# janus.net
KiCad netlist of a schematic drawn in EAGLE
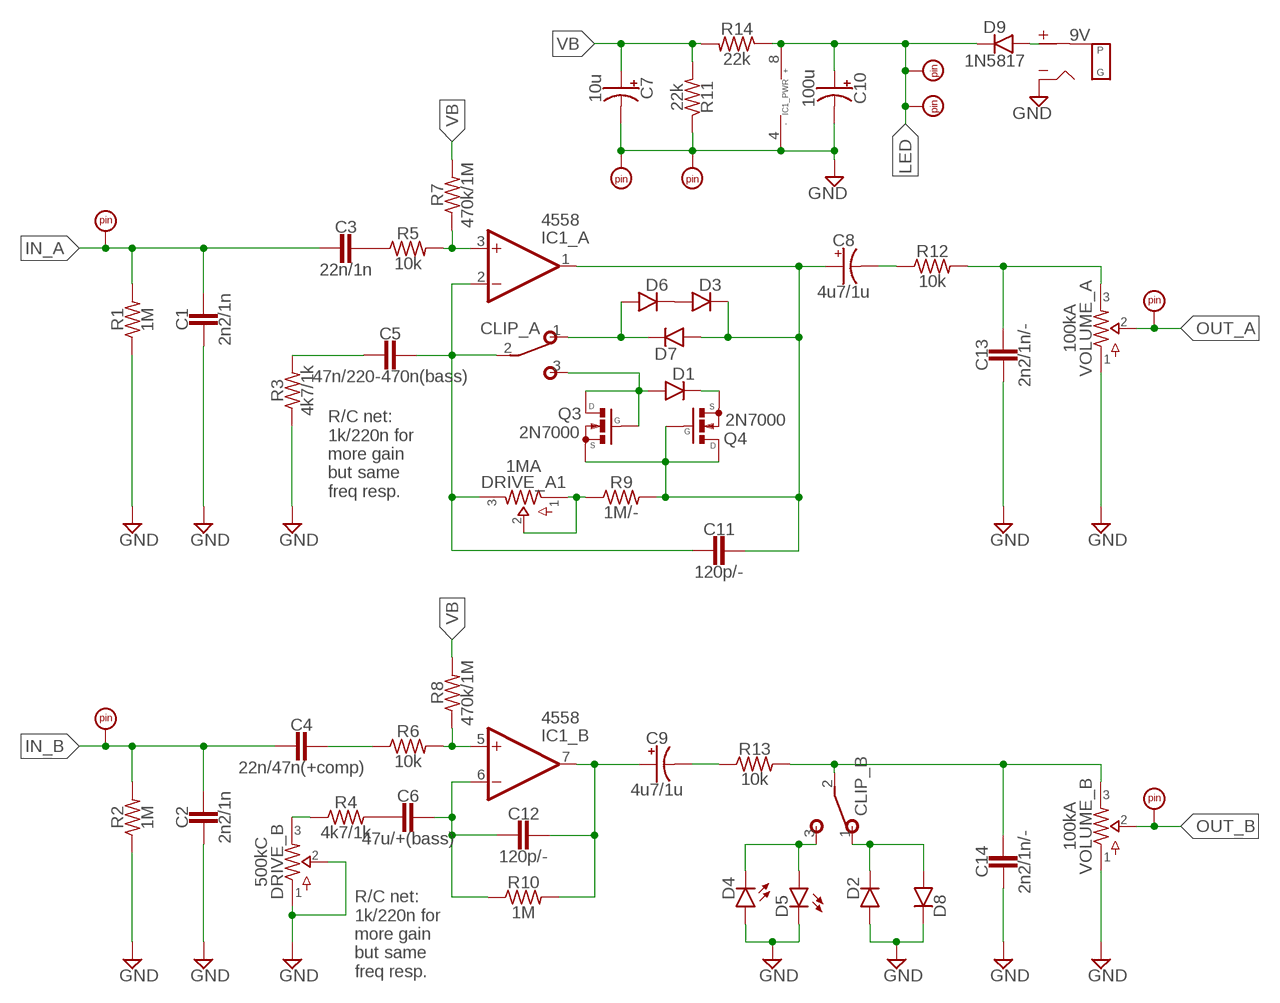
[diagram p0: schematic, sheet 1]

(export (version "E")
  (design (tool "Eeschema 10.0.6"))
  (components
    (comp (ref "9V")
      (value "DC_MONO")
      (footprint "eagle-import:DC")
      (libsource (lib "eagle-import") (part "DC_MONO"))
    )
    (comp (ref "C1")
      (value "2n2/1n")
      (footprint "eagle-import:050X030_025_2")
      (libsource (lib "eagle-import") (part "CER/FILM2"))
    )
    (comp (ref "C2")
      (value "2n2/1n")
      (footprint "eagle-import:050X030_025_2")
      (libsource (lib "eagle-import") (part "CER/FILM2"))
    )
    (comp (ref "C3")
      (value "22n/1n")
      (footprint "eagle-import:050X030_025_2")
      (libsource (lib "eagle-import") (part "CER/FILM2"))
    )
    (comp (ref "C4")
      (value "22n/47n(+comp)")
      (footprint "eagle-import:050X030_025_2")
      (libsource (lib "eagle-import") (part "CER/FILM2"))
    )
    (comp (ref "C5")
      (value "47n/220-470n(bass)")
      (footprint "eagle-import:050X030_025_2")
      (libsource (lib "eagle-import") (part "CER/FILM2"))
    )
    (comp (ref "C6")
      (value "47u/+(bass)")
      (footprint "eagle-import:050X030_025_2")
      (libsource (lib "eagle-import") (part "CER/FILM2"))
    )
    (comp (ref "C7")
      (value "10u")
      (footprint "eagle-import:050_020_1")
      (libsource (lib "eagle-import") (part "0501"))
    )
    (comp (ref "C8")
      (value "4u7/1u")
      (footprint "eagle-import:050_020_1")
      (libsource (lib "eagle-import") (part "0501"))
    )
    (comp (ref "C9")
      (value "4u7/1u")
      (footprint "eagle-import:050_020_1")
      (libsource (lib "eagle-import") (part "0501"))
    )
    (comp (ref "C10")
      (value "100u")
      (footprint "eagle-import:050_020_1")
      (libsource (lib "eagle-import") (part "0501"))
    )
    (comp (ref "C11")
      (value "120p/-")
      (footprint "eagle-import:050X030_025_2")
      (libsource (lib "eagle-import") (part "CER/FILM2"))
    )
    (comp (ref "C12")
      (value "120p/-")
      (footprint "eagle-import:050X030_025_2")
      (libsource (lib "eagle-import") (part "CER/FILM2"))
    )
    (comp (ref "C13")
      (value "2n2/1n/-")
      (footprint "eagle-import:050X030_025_2")
      (libsource (lib "eagle-import") (part "CER/FILM2"))
    )
    (comp (ref "C14")
      (value "2n2/1n/-")
      (footprint "eagle-import:050X030_025_2")
      (libsource (lib "eagle-import") (part "CER/FILM2"))
    )
    (comp (ref "CLIP_A")
      (value "SPDTPADS")
      (footprint "eagle-import:SPDT")
      (libsource (lib "eagle-import") (part "SPDTPADS"))
    )
    (comp (ref "CLIP_B")
      (value "SPDTPADS")
      (footprint "eagle-import:SPDT")
      (libsource (lib "eagle-import") (part "SPDTPADS"))
    )
    (comp (ref "D1")
      (value "DO35.2")
      (footprint "eagle-import:DO35-2")
      (libsource (lib "eagle-import") (part "DO35.2"))
    )
    (comp (ref "D2")
      (value "DO35.2")
      (footprint "eagle-import:DO35-2")
      (libsource (lib "eagle-import") (part "DO35.2"))
    )
    (comp (ref "D3")
      (value "DO35.2")
      (footprint "eagle-import:DO35-2")
      (libsource (lib "eagle-import") (part "DO35.2"))
    )
    (comp (ref "D4")
      (value "LEDB")
      (footprint "eagle-import:3MM_B")
      (libsource (lib "eagle-import") (part "LEDB"))
    )
    (comp (ref "D5")
      (value "LEDB")
      (footprint "eagle-import:3MM_B")
      (libsource (lib "eagle-import") (part "LEDB"))
    )
    (comp (ref "D6")
      (value "DO35.2")
      (footprint "eagle-import:DO35-2")
      (libsource (lib "eagle-import") (part "DO35.2"))
    )
    (comp (ref "D7")
      (value "DO35.2")
      (footprint "eagle-import:DO35-2")
      (libsource (lib "eagle-import") (part "DO35.2"))
    )
    (comp (ref "D8")
      (value "DO35.2")
      (footprint "eagle-import:DO35-2")
      (libsource (lib "eagle-import") (part "DO35.2"))
    )
    (comp (ref "D9")
      (value "1N5817")
      (footprint "eagle-import:DO41-3")
      (libsource (lib "eagle-import") (part "DO41.3"))
    )
    (comp (ref "DRIVE_A1")
      (value "1MA")
      (footprint "eagle-import:16MM")
      (libsource (lib "eagle-import") (part "POTS16MM"))
    )
    (comp (ref "DRIVE_B")
      (value "500kC")
      (footprint "eagle-import:16MM")
      (libsource (lib "eagle-import") (part "POTS16MM"))
    )
    (comp (ref "GNDA")
      (value "PADRND")
      (footprint "eagle-import:ROUND")
      (libsource (lib "eagle-import") (part "PADRND"))
    )
    (comp (ref "GNDB")
      (value "PADRND")
      (footprint "eagle-import:ROUND")
      (libsource (lib "eagle-import") (part "PADRND"))
    )
    (comp (ref "IC1")
      (value "4558")
      (footprint "eagle-import:DIL08")
      (libsource (lib "eagle-import") (part "DUALTH"))
    )
    (comp (ref "INA")
      (value "PADSQR")
      (footprint "eagle-import:SQUARE")
      (libsource (lib "eagle-import") (part "PADSQR"))
    )
    (comp (ref "INB")
      (value "PADSQR")
      (footprint "eagle-import:SQUARE")
      (libsource (lib "eagle-import") (part "PADSQR"))
    )
    (comp (ref "LEDA")
      (value "PADRND")
      (footprint "eagle-import:ROUND")
      (libsource (lib "eagle-import") (part "PADRND"))
    )
    (comp (ref "LEDB")
      (value "PADRND")
      (footprint "eagle-import:ROUND")
      (libsource (lib "eagle-import") (part "PADRND"))
    )
    (comp (ref "OUTA")
      (value "PADSQR")
      (footprint "eagle-import:SQUARE")
      (libsource (lib "eagle-import") (part "PADSQR"))
    )
    (comp (ref "OUTB")
      (value "PADSQR")
      (footprint "eagle-import:SQUARE")
      (libsource (lib "eagle-import") (part "PADSQR"))
    )
    (comp (ref "Q3")
      (value "2N7000")
      (footprint "eagle-import:SOT54ES")
      (libsource (lib "eagle-import") (part "BS170"))
    )
    (comp (ref "Q4")
      (value "2N7000")
      (footprint "eagle-import:SOT54ES")
      (libsource (lib "eagle-import") (part "BS170"))
    )
    (comp (ref "R1")
      (value "1M")
      (footprint "eagle-import:R0207_3")
      (libsource (lib "eagle-import") (part "R_.3B"))
    )
    (comp (ref "R2")
      (value "1M")
      (footprint "eagle-import:R0207_3")
      (libsource (lib "eagle-import") (part "R_.3B"))
    )
    (comp (ref "R3")
      (value "4k7/1k")
      (footprint "eagle-import:R0207_3")
      (libsource (lib "eagle-import") (part "R_.3B"))
    )
    (comp (ref "R4")
      (value "4k7/1k")
      (footprint "eagle-import:R0207_3")
      (libsource (lib "eagle-import") (part "R_.3B"))
    )
    (comp (ref "R5")
      (value "10k")
      (footprint "eagle-import:R0207_3")
      (libsource (lib "eagle-import") (part "R_.3B"))
    )
    (comp (ref "R6")
      (value "10k")
      (footprint "eagle-import:R0207_3")
      (libsource (lib "eagle-import") (part "R_.3B"))
    )
    (comp (ref "R7")
      (value "470k/1M")
      (footprint "eagle-import:R0207_3")
      (libsource (lib "eagle-import") (part "R_.3B"))
    )
    (comp (ref "R8")
      (value "470k/1M")
      (footprint "eagle-import:R0207_3")
      (libsource (lib "eagle-import") (part "R_.3B"))
    )
    (comp (ref "R9")
      (value "1M/-")
      (footprint "eagle-import:R0207_3")
      (libsource (lib "eagle-import") (part "R_.3B"))
    )
    (comp (ref "R10")
      (value "1M")
      (footprint "eagle-import:R0207_3")
      (libsource (lib "eagle-import") (part "R_.3B"))
    )
    (comp (ref "R11")
      (value "22k")
      (footprint "eagle-import:R0207_3")
      (libsource (lib "eagle-import") (part "R_.3B"))
    )
    (comp (ref "R12")
      (value "10k")
      (footprint "eagle-import:R0207_3")
      (libsource (lib "eagle-import") (part "R_.3B"))
    )
    (comp (ref "R13")
      (value "10k")
      (footprint "eagle-import:R0207_3")
      (libsource (lib "eagle-import") (part "R_.3B"))
    )
    (comp (ref "R14")
      (value "22k")
      (footprint "eagle-import:R0207_3")
      (libsource (lib "eagle-import") (part "R_.3B"))
    )
    (comp (ref "VOLUME_A")
      (value "100kA")
      (footprint "eagle-import:16MM")
      (libsource (lib "eagle-import") (part "POTS16MM"))
    )
    (comp (ref "VOLUME_B")
      (value "100kA")
      (footprint "eagle-import:16MM")
      (libsource (lib "eagle-import") (part "POTS16MM"))
    )
  )
  (nets
    (net (code "1") (name "GND") (class "Default")
      (node (ref "9V") (pin "S") (pinfunction "SLEEVE_S") (pintype "passive"))
      (node (ref "C1") (pin "2") (pinfunction "2_2") (pintype "passive"))
      (node (ref "C10") (pin "-") (pinfunction "-_-") (pintype "passive"))
      (node (ref "C13") (pin "2") (pinfunction "2_2") (pintype "passive"))
      (node (ref "C14") (pin "2") (pinfunction "2_2") (pintype "passive"))
      (node (ref "C2") (pin "2") (pinfunction "2_2") (pintype "passive"))
      (node (ref "C7") (pin "-") (pinfunction "-_-") (pintype "passive"))
      (node (ref "D2") (pin "A") (pinfunction "A_A") (pintype "passive"))
      (node (ref "D4") (pin "A") (pinfunction "A_A") (pintype "passive"))
      (node (ref "D5") (pin "K") (pinfunction "C_K") (pintype "passive"))
      (node (ref "D8") (pin "C") (pinfunction "C_C") (pintype "passive"))
      (node (ref "DRIVE_B") (pin "1") (pinfunction "1_1") (pintype "passive"))
      (node (ref "DRIVE_B") (pin "2") (pinfunction "2_2") (pintype "passive"))
      (node (ref "GNDA") (pin "1") (pinfunction "P$1_1") (pintype "bidirectional"))
      (node (ref "GNDB") (pin "1") (pinfunction "P$1_1") (pintype "bidirectional"))
      (node (ref "IC1") (pin "4") (pinfunction "V-_4") (pintype "power_in"))
      (node (ref "R1") (pin "1") (pinfunction "1_1") (pintype "passive"))
      (node (ref "R11") (pin "1") (pinfunction "1_1") (pintype "passive"))
      (node (ref "R2") (pin "1") (pinfunction "1_1") (pintype "passive"))
      (node (ref "R3") (pin "1") (pinfunction "1_1") (pintype "passive"))
      (node (ref "VOLUME_A") (pin "1") (pinfunction "1_1") (pintype "passive"))
      (node (ref "VOLUME_B") (pin "1") (pinfunction "1_1") (pintype "passive"))
    )
    (net (code "2") (name "IN_A") (class "Default")
      (node (ref "C1") (pin "1") (pinfunction "1_1") (pintype "passive"))
      (node (ref "C3") (pin "2") (pinfunction "2_2") (pintype "passive"))
      (node (ref "INA") (pin "1") (pinfunction "P$1_1") (pintype "bidirectional"))
      (node (ref "R1") (pin "2") (pinfunction "2_2") (pintype "passive"))
    )
    (net (code "3") (name "IN_B") (class "Default")
      (node (ref "C2") (pin "1") (pinfunction "1_1") (pintype "passive"))
      (node (ref "C4") (pin "2") (pinfunction "2_2") (pintype "passive"))
      (node (ref "INB") (pin "1") (pinfunction "P$1_1") (pintype "bidirectional"))
      (node (ref "R2") (pin "2") (pinfunction "2_2") (pintype "passive"))
    )
    (net (code "4") (name "LED") (class "Default")
      (node (ref "C10") (pin "+") (pinfunction "+_+") (pintype "passive"))
      (node (ref "D9") (pin "C") (pinfunction "C_C") (pintype "passive"))
      (node (ref "IC1") (pin "8") (pinfunction "V+_8") (pintype "power_in"))
      (node (ref "LEDA") (pin "1") (pinfunction "P$1_1") (pintype "bidirectional"))
      (node (ref "LEDB") (pin "1") (pinfunction "P$1_1") (pintype "bidirectional"))
      (node (ref "R14") (pin "1") (pinfunction "1_1") (pintype "passive"))
    )
    (net (code "5") (name "Net-(9V-TIP)") (class "Default")
      (node (ref "9V") (pin "T") (pinfunction "TIP_T") (pintype "passive"))
      (node (ref "D9") (pin "A") (pinfunction "A_A") (pintype "passive"))
    )
    (net (code "6") (name "Net-(C3-Pad1)") (class "Default")
      (node (ref "C3") (pin "1") (pinfunction "1_1") (pintype "passive"))
      (node (ref "R5") (pin "1") (pinfunction "1_1") (pintype "passive"))
    )
    (net (code "7") (name "Net-(C4-Pad1)") (class "Default")
      (node (ref "C4") (pin "1") (pinfunction "1_1") (pintype "passive"))
      (node (ref "R6") (pin "1") (pinfunction "1_1") (pintype "passive"))
    )
    (net (code "8") (name "Net-(C5-Pad2)") (class "Default")
      (node (ref "C5") (pin "2") (pinfunction "2_2") (pintype "passive"))
      (node (ref "R3") (pin "2") (pinfunction "2_2") (pintype "passive"))
    )
    (net (code "9") (name "Net-(C6-Pad2)") (class "Default")
      (node (ref "C6") (pin "2") (pinfunction "2_2") (pintype "passive"))
      (node (ref "R4") (pin "2") (pinfunction "2_2") (pintype "passive"))
    )
    (net (code "10") (name "Net-(C8-Pad-)") (class "Default")
      (node (ref "C8") (pin "-") (pinfunction "-_-") (pintype "passive"))
      (node (ref "R12") (pin "1") (pinfunction "1_1") (pintype "passive"))
    )
    (net (code "11") (name "Net-(C9-Pad-)") (class "Default")
      (node (ref "C9") (pin "-") (pinfunction "-_-") (pintype "passive"))
      (node (ref "R13") (pin "1") (pinfunction "1_1") (pintype "passive"))
    )
    (net (code "12") (name "Net-(C13-Pad1)") (class "Default")
      (node (ref "C13") (pin "1") (pinfunction "1_1") (pintype "passive"))
      (node (ref "R12") (pin "2") (pinfunction "2_2") (pintype "passive"))
      (node (ref "VOLUME_A") (pin "3") (pinfunction "3_3") (pintype "passive"))
    )
    (net (code "13") (name "Net-(CLIP_A-O)") (class "Default")
      (node (ref "CLIP_A") (pin "1") (pinfunction "O_1") (pintype "passive"))
      (node (ref "D6") (pin "A") (pinfunction "A_A") (pintype "passive"))
      (node (ref "D7") (pin "C") (pinfunction "C_C") (pintype "passive"))
    )
    (net (code "14") (name "Net-(CLIP_A-P)") (class "Default")
      (node (ref "C11") (pin "2") (pinfunction "2_2") (pintype "passive"))
      (node (ref "C5") (pin "1") (pinfunction "1_1") (pintype "passive"))
      (node (ref "CLIP_A") (pin "2") (pinfunction "P_2") (pintype "passive"))
      (node (ref "DRIVE_A1") (pin "3") (pinfunction "3_3") (pintype "passive"))
      (node (ref "IC1") (pin "2") (pinfunction "-IN_2") (pintype "input"))
    )
    (net (code "15") (name "Net-(CLIP_A-S)") (class "Default")
      (node (ref "CLIP_A") (pin "3") (pinfunction "S_3") (pintype "passive"))
      (node (ref "D1") (pin "A") (pinfunction "A_A") (pintype "passive"))
      (node (ref "Q3") (pin "D") (pinfunction "D_D") (pintype "passive"))
      (node (ref "Q3") (pin "G") (pinfunction "G_G") (pintype "passive"))
    )
    (net (code "16") (name "Net-(CLIP_B-O)") (class "Default")
      (node (ref "CLIP_B") (pin "1") (pinfunction "O_1") (pintype "passive"))
      (node (ref "D2") (pin "C") (pinfunction "C_C") (pintype "passive"))
      (node (ref "D8") (pin "A") (pinfunction "A_A") (pintype "passive"))
    )
    (net (code "17") (name "Net-(CLIP_B-P)") (class "Default")
      (node (ref "C14") (pin "1") (pinfunction "1_1") (pintype "passive"))
      (node (ref "CLIP_B") (pin "2") (pinfunction "P_2") (pintype "passive"))
      (node (ref "R13") (pin "2") (pinfunction "2_2") (pintype "passive"))
      (node (ref "VOLUME_B") (pin "3") (pinfunction "3_3") (pintype "passive"))
    )
    (net (code "18") (name "Net-(CLIP_B-S)") (class "Default")
      (node (ref "CLIP_B") (pin "3") (pinfunction "S_3") (pintype "passive"))
      (node (ref "D4") (pin "K") (pinfunction "C_K") (pintype "passive"))
      (node (ref "D5") (pin "A") (pinfunction "A_A") (pintype "passive"))
    )
    (net (code "19") (name "Net-(D1-PadC)") (class "Default")
      (node (ref "D1") (pin "C") (pinfunction "C_C") (pintype "passive"))
      (node (ref "Q4") (pin "S") (pinfunction "S_S") (pintype "passive"))
    )
    (net (code "20") (name "Net-(D3-PadA)") (class "Default")
      (node (ref "D3") (pin "A") (pinfunction "A_A") (pintype "passive"))
      (node (ref "D6") (pin "C") (pinfunction "C_C") (pintype "passive"))
    )
    (net (code "21") (name "Net-(DRIVE_A1-Pad1)") (class "Default")
      (node (ref "DRIVE_A1") (pin "1") (pinfunction "1_1") (pintype "passive"))
      (node (ref "DRIVE_A1") (pin "2") (pinfunction "2_2") (pintype "passive"))
      (node (ref "R9") (pin "1") (pinfunction "1_1") (pintype "passive"))
    )
    (net (code "22") (name "Net-(DRIVE_B-Pad3)") (class "Default")
      (node (ref "DRIVE_B") (pin "3") (pinfunction "3_3") (pintype "passive"))
      (node (ref "R4") (pin "1") (pinfunction "1_1") (pintype "passive"))
    )
    (net (code "23") (name "Net-(IC1A-+IN)") (class "Default")
      (node (ref "IC1") (pin "3") (pinfunction "+IN_3") (pintype "input"))
      (node (ref "R5") (pin "2") (pinfunction "2_2") (pintype "passive"))
      (node (ref "R7") (pin "1") (pinfunction "1_1") (pintype "passive"))
    )
    (net (code "24") (name "Net-(IC1A-OUT)") (class "Default")
      (node (ref "C11") (pin "1") (pinfunction "1_1") (pintype "passive"))
      (node (ref "C8") (pin "+") (pinfunction "+_+") (pintype "passive"))
      (node (ref "D3") (pin "C") (pinfunction "C_C") (pintype "passive"))
      (node (ref "D7") (pin "A") (pinfunction "A_A") (pintype "passive"))
      (node (ref "IC1") (pin "1") (pinfunction "OUT_1") (pintype "output"))
      (node (ref "Q3") (pin "S") (pinfunction "S_S") (pintype "passive"))
      (node (ref "Q4") (pin "D") (pinfunction "D_D") (pintype "passive"))
      (node (ref "Q4") (pin "G") (pinfunction "G_G") (pintype "passive"))
      (node (ref "R9") (pin "2") (pinfunction "2_2") (pintype "passive"))
    )
    (net (code "25") (name "Net-(IC1B-+IN)") (class "Default")
      (node (ref "IC1") (pin "5") (pinfunction "+IN_5") (pintype "input"))
      (node (ref "R6") (pin "2") (pinfunction "2_2") (pintype "passive"))
      (node (ref "R8") (pin "1") (pinfunction "1_1") (pintype "passive"))
    )
    (net (code "26") (name "Net-(IC1B--IN)") (class "Default")
      (node (ref "C12") (pin "2") (pinfunction "2_2") (pintype "passive"))
      (node (ref "C6") (pin "1") (pinfunction "1_1") (pintype "passive"))
      (node (ref "IC1") (pin "6") (pinfunction "-IN_6") (pintype "input"))
      (node (ref "R10") (pin "1") (pinfunction "1_1") (pintype "passive"))
    )
    (net (code "27") (name "Net-(IC1B-OUT)") (class "Default")
      (node (ref "C12") (pin "1") (pinfunction "1_1") (pintype "passive"))
      (node (ref "C9") (pin "+") (pinfunction "+_+") (pintype "passive"))
      (node (ref "IC1") (pin "7") (pinfunction "OUT_7") (pintype "output"))
      (node (ref "R10") (pin "2") (pinfunction "2_2") (pintype "passive"))
    )
    (net (code "28") (name "OUT_A") (class "Default")
      (node (ref "OUTA") (pin "1") (pinfunction "P$1_1") (pintype "bidirectional"))
      (node (ref "VOLUME_A") (pin "2") (pinfunction "2_2") (pintype "passive"))
    )
    (net (code "29") (name "OUT_B") (class "Default")
      (node (ref "OUTB") (pin "1") (pinfunction "P$1_1") (pintype "bidirectional"))
      (node (ref "VOLUME_B") (pin "2") (pinfunction "2_2") (pintype "passive"))
    )
    (net (code "30") (name "VB") (class "Default")
      (node (ref "C7") (pin "+") (pinfunction "+_+") (pintype "passive"))
      (node (ref "R11") (pin "2") (pinfunction "2_2") (pintype "passive"))
      (node (ref "R14") (pin "2") (pinfunction "2_2") (pintype "passive"))
      (node (ref "R7") (pin "2") (pinfunction "2_2") (pintype "passive"))
      (node (ref "R8") (pin "2") (pinfunction "2_2") (pintype "passive"))
    )
  )
)
